# RPI_3.net
KiCad netlist of a schematic drawn in Altium Designer
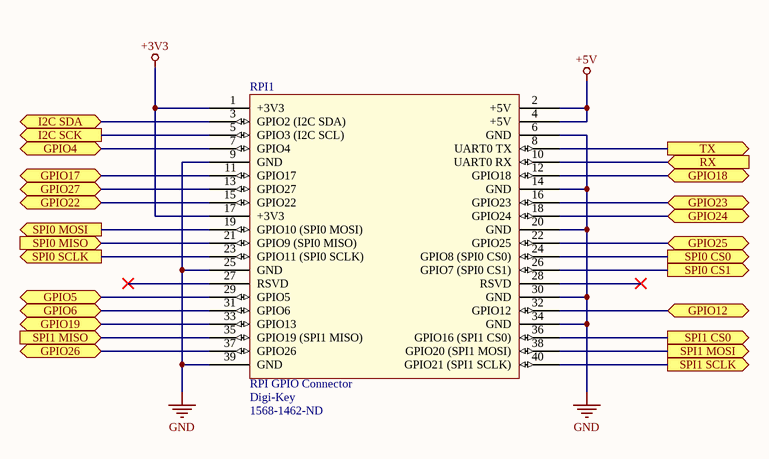
[diagram p0: RPI 3.SchDoc]

(export (version "E")
  (design (tool "Eeschema 10.0.6"))
  (components
    (comp (ref "RPI1")
      (value "RPI GPIO Connector")
      (footprint "rpi")
      (description "GPIO Header for Raspberry Pi A+/B+/Pi 2/Pi 3 - 2x20")
      (fields
        (field (name "MANUFACTURER") "SparkFun Electronics")
        (field (name "MANUFACTURER PART NUMBER") "PRT-14017")
        (field (name "SUPPLIER 1") "Digi-Key")
        (field (name "SUPPLIER PART NUMBER 1") "1568-1462-ND")
      )
      (libsource (lib "rpi") (part "rpi connector"))
    )
  )
  (nets
    (net (code "1") (name "+3V3") (class "Default")
      (node (ref "RPI1") (pin "1") (pinfunction "+3V3_1") (pintype "power_in"))
      (node (ref "RPI1") (pin "17") (pinfunction "+3V3_17") (pintype "power_in"))
    )
    (net (code "2") (name "+5V") (class "Default")
      (node (ref "RPI1") (pin "2") (pinfunction "+5V_2") (pintype "power_in"))
      (node (ref "RPI1") (pin "4") (pinfunction "+5V_4") (pintype "power_in"))
    )
    (net (code "3") (name "/GPIO4") (class "Default")
      (node (ref "RPI1") (pin "7") (pinfunction "GPIO4_7") (pintype "bidirectional"))
    )
    (net (code "4") (name "/GPIO5") (class "Default")
      (node (ref "RPI1") (pin "29") (pinfunction "GPIO5_29") (pintype "bidirectional"))
    )
    (net (code "5") (name "/GPIO6") (class "Default")
      (node (ref "RPI1") (pin "31") (pinfunction "GPIO6_31") (pintype "bidirectional"))
    )
    (net (code "6") (name "/GPIO12") (class "Default")
      (node (ref "RPI1") (pin "32") (pinfunction "GPIO12_32") (pintype "bidirectional"))
    )
    (net (code "7") (name "/GPIO17") (class "Default")
      (node (ref "RPI1") (pin "11") (pinfunction "GPIO17_11") (pintype "bidirectional"))
    )
    (net (code "8") (name "/GPIO18") (class "Default")
      (node (ref "RPI1") (pin "12") (pinfunction "GPIO18_12") (pintype "bidirectional"))
    )
    (net (code "9") (name "/GPIO19") (class "Default")
      (node (ref "RPI1") (pin "33") (pinfunction "GPIO13_33") (pintype "bidirectional"))
    )
    (net (code "10") (name "/GPIO22") (class "Default")
      (node (ref "RPI1") (pin "15") (pinfunction "GPIO22_15") (pintype "bidirectional"))
    )
    (net (code "11") (name "/GPIO23") (class "Default")
      (node (ref "RPI1") (pin "16") (pinfunction "GPIO23_16") (pintype "bidirectional"))
    )
    (net (code "12") (name "/GPIO24") (class "Default")
      (node (ref "RPI1") (pin "18") (pinfunction "GPIO24_18") (pintype "bidirectional"))
    )
    (net (code "13") (name "/GPIO25") (class "Default")
      (node (ref "RPI1") (pin "22") (pinfunction "GPIO25_22") (pintype "bidirectional"))
    )
    (net (code "14") (name "/GPIO26") (class "Default")
      (node (ref "RPI1") (pin "37") (pinfunction "GPIO26_37") (pintype "bidirectional"))
    )
    (net (code "15") (name "/GPIO27") (class "Default")
      (node (ref "RPI1") (pin "13") (pinfunction "GPIO27_13") (pintype "bidirectional"))
    )
    (net (code "16") (name "/I2C SCK") (class "Default")
      (node (ref "RPI1") (pin "5") (pinfunction "GPIO3_(I2C_SCL)_5") (pintype "bidirectional"))
    )
    (net (code "17") (name "/I2C SDA") (class "Default")
      (node (ref "RPI1") (pin "3") (pinfunction "GPIO2_(I2C_SDA)_3") (pintype "bidirectional"))
    )
    (net (code "18") (name "/RX") (class "Default")
      (node (ref "RPI1") (pin "10") (pinfunction "UART0_RX_10") (pintype "bidirectional"))
    )
    (net (code "19") (name "/SPI0 CS0") (class "Default")
      (node (ref "RPI1") (pin "24") (pinfunction "GPIO8_(SPI0_CS0)_24") (pintype "bidirectional"))
    )
    (net (code "20") (name "/SPI0 CS1") (class "Default")
      (node (ref "RPI1") (pin "26") (pinfunction "GPIO7_(SPI0_CS1)_26") (pintype "bidirectional"))
    )
    (net (code "21") (name "/SPI0 MISO") (class "Default")
      (node (ref "RPI1") (pin "21") (pinfunction "GPIO9_(SPI0_MISO)_21") (pintype "bidirectional"))
    )
    (net (code "22") (name "/SPI0 MOSI") (class "Default")
      (node (ref "RPI1") (pin "19") (pinfunction "GPIO10_(SPI0_MOSI)_19") (pintype "bidirectional"))
    )
    (net (code "23") (name "/SPI0 SCLK") (class "Default")
      (node (ref "RPI1") (pin "23") (pinfunction "GPIO11_(SPI0_SCLK)_23") (pintype "bidirectional"))
    )
    (net (code "24") (name "/SPI1 CS0") (class "Default")
      (node (ref "RPI1") (pin "36") (pinfunction "GPIO16_(SPI1_CS0)_36") (pintype "bidirectional"))
    )
    (net (code "25") (name "/SPI1 MISO") (class "Default")
      (node (ref "RPI1") (pin "35") (pinfunction "GPIO19_(SPI1_MISO)_35") (pintype "bidirectional"))
    )
    (net (code "26") (name "/SPI1 MOSI") (class "Default")
      (node (ref "RPI1") (pin "38") (pinfunction "GPIO20_(SPI1_MOSI)_38") (pintype "bidirectional"))
    )
    (net (code "27") (name "/SPI1 SCLK") (class "Default")
      (node (ref "RPI1") (pin "40") (pinfunction "GPIO21_(SPI1_SCLK)_40") (pintype "bidirectional"))
    )
    (net (code "28") (name "/TX") (class "Default")
      (node (ref "RPI1") (pin "8") (pinfunction "UART0_TX_8") (pintype "bidirectional"))
    )
    (net (code "29") (name "GND") (class "Default")
      (node (ref "RPI1") (pin "14") (pinfunction "GND_14") (pintype "power_in"))
      (node (ref "RPI1") (pin "20") (pinfunction "GND_20") (pintype "power_in"))
      (node (ref "RPI1") (pin "25") (pinfunction "GND_25") (pintype "power_in"))
      (node (ref "RPI1") (pin "30") (pinfunction "GND_30") (pintype "power_in"))
      (node (ref "RPI1") (pin "34") (pinfunction "GND_34") (pintype "passive"))
      (node (ref "RPI1") (pin "39") (pinfunction "GND_39") (pintype "power_in"))
      (node (ref "RPI1") (pin "6") (pinfunction "GND_6") (pintype "power_in"))
      (node (ref "RPI1") (pin "9") (pinfunction "GND_9") (pintype "power_in"))
    )
    (net (code "30") (name "unconnected-(RPI1-RSVD-Pad27)") (class "Default")
      (node (ref "RPI1") (pin "27") (pinfunction "RSVD_27") (pintype "passive+no_connect"))
    )
    (net (code "31") (name "unconnected-(RPI1-RSVD-Pad28)") (class "Default")
      (node (ref "RPI1") (pin "28") (pinfunction "RSVD_28") (pintype "passive+no_connect"))
    )
  )
)
